# can.net
KiCad netlist of a schematic drawn in Altium Designer
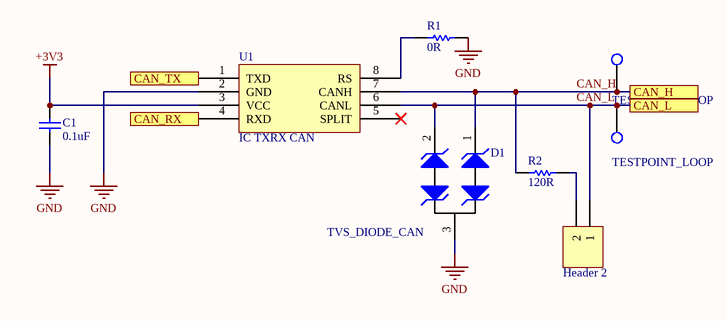
[diagram p0: can.SchDoc]

(export (version "E")
  (design (tool "Eeschema 10.0.6"))
  (components
    (comp (ref "1")
      (value "Header 2")
      (footprint "HDR1X2")
      (description "Header, 2-Pin")
      (fields (field (name "PUBLISHER") "Altium Limited"))
      (libsource (lib "Miscellaneous Connectors") (part "Header 2"))
    )
    (comp (ref "C1")
      (value "0.1uF")
      (footprint "CAPC0603(1608)55_N")
      (description "CAP CER 0.1UF 16V X7R 0603")
      (fields (field (name "MANUFACTURER") "Yageo") (field (name "MPN") "CC0603KRX7R7BB104"))
      (libsource (lib "UWRT_Schematic_Library_2019") (part "CAP_0.1uF_16V_0603"))
    )
    (comp (ref "CANH1")
      (value "TESTPOINT_LOOP")
      (footprint "TESTPOINT_LOOP")
      (libsource (lib "UWRT_Schematic_Library_2019") (part "TESTPOINT_LOOP"))
    )
    (comp (ref "CANL1")
      (value "TESTPOINT_LOOP")
      (footprint "TESTPOINT_LOOP")
      (libsource (lib "UWRT_Schematic_Library_2019") (part "TESTPOINT_LOOP"))
    )
    (comp (ref "D1")
      (value "TVS_DIODE_CAN")
      (footprint "UWRT_Footprint_Library_2019:TVS_DIODE_CAN")
      (description "TVS DIODE 24V 41V SOT323-3")
      (fields (field (name "MANUFACTURER") "Nexperia USA Inc.") (field (name "MPN") "PESD2CAN,215"))
      (libsource (lib "UWRT_Schematic_Library_2019") (part "TVS_DIODE_CAN"))
    )
    (comp (ref "R1")
      (value "0R")
      (footprint "RESC0603(1608)_N")
      (description "RES SMD 0 OHM JUMPER 1/10W 0603")
      (fields (field (name "MANUFACTURER") "Yageo") (field (name "MPN") "RC0603JR-070RL"))
      (libsource (lib "UWRT_Schematic_Library_2019") (part "RES_0R_0603"))
    )
    (comp (ref "R2")
      (value "120R")
      (footprint "RESC0603(1608)_N")
      (description "RES SMD 120 OHM 5% 1/10W 0603")
      (fields (field (name "MANUFACTURER") "Yageo") (field (name "TOLERANCE") "5%"))
      (libsource (lib "UWRT_Schematic_Library_2019") (part "RES_120R_0603"))
    )
    (comp (ref "U1")
      (value "IC TXRX CAN")
      (footprint "LT-S8_N")
      (description "IC TXRX CAN 4MBPS 8SO")
      (fields (field (name "MANUFACTURER") "Linear Technologies") (field (name "MPN") "LTC2875IS8#PBF"))
      (libsource (lib "UWRT_Schematic_Library_2019") (part "LTC2875"))
    )
  )
  (nets
    (net (code "1") (name "+3V3") (class "Default")
      (node (ref "C1") (pin "2") (pinfunction "2_2") (pintype "passive"))
      (node (ref "U1") (pin "3") (pinfunction "VCC_3") (pintype "passive"))
    )
    (net (code "2") (name "/CAN_H") (class "Default")
      (node (ref "CANH1") (pin "1") (pinfunction "=value_1") (pintype "passive"))
      (node (ref "D1") (pin "1") (pinfunction "1_1") (pintype "passive"))
      (node (ref "R2") (pin "1") (pinfunction "1_1") (pintype "passive"))
      (node (ref "U1") (pin "7") (pinfunction "CANH_7") (pintype "passive"))
    )
    (net (code "3") (name "/CAN_L") (class "Default")
      (node (ref "1") (pin "1") (pinfunction "1_1") (pintype "passive"))
      (node (ref "CANL1") (pin "1") (pinfunction "=value_1") (pintype "passive"))
      (node (ref "D1") (pin "2") (pinfunction "2_2") (pintype "passive"))
      (node (ref "U1") (pin "6") (pinfunction "CANL_6") (pintype "passive"))
    )
    (net (code "4") (name "/CAN_RX") (class "Default")
      (node (ref "U1") (pin "4") (pinfunction "RXD_4") (pintype "passive"))
    )
    (net (code "5") (name "/CAN_TX") (class "Default")
      (node (ref "U1") (pin "1") (pinfunction "TXD_1") (pintype "passive"))
    )
    (net (code "6") (name "GND") (class "Default")
      (node (ref "C1") (pin "1") (pinfunction "1_1") (pintype "passive"))
      (node (ref "D1") (pin "3") (pinfunction "3_3") (pintype "passive"))
      (node (ref "R1") (pin "2") (pinfunction "2_2") (pintype "passive"))
      (node (ref "U1") (pin "2") (pinfunction "GND_2") (pintype "passive"))
    )
    (net (code "7") (name "Net-(1-Pad2)") (class "Default")
      (node (ref "1") (pin "2") (pinfunction "2_2") (pintype "passive"))
      (node (ref "R2") (pin "2") (pinfunction "2_2") (pintype "passive"))
    )
    (net (code "8") (name "Net-(U1-RS)") (class "Default")
      (node (ref "R1") (pin "1") (pinfunction "1_1") (pintype "passive"))
      (node (ref "U1") (pin "8") (pinfunction "RS_8") (pintype "passive"))
    )
    (net (code "9") (name "unconnected-(U1-SPLIT-Pad5)") (class "Default")
      (node (ref "U1") (pin "5") (pinfunction "SPLIT_5") (pintype "passive+no_connect"))
    )
  )
)
